# 8-pin_SOIC_TSSOP.net
KiCad netlist of a schematic drawn in EAGLE
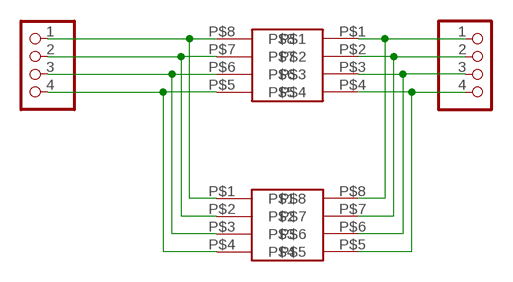
[diagram p0: schematic, sheet 1]

(export (version "E")
  (design (tool "Eeschema 10.0.6"))
  (components
    (comp (ref "CN1")
      (value "PADS-4")
      (footprint "eagle-import:PADS-4")
      (libsource (lib "eagle-import") (part "PADS-4"))
    )
    (comp (ref "CN2")
      (value "PADS-4")
      (footprint "eagle-import:PADS-4")
      (libsource (lib "eagle-import") (part "PADS-4"))
    )
    (comp (ref "U$1")
      (value "8-PINSOIC-NW")
      (footprint "eagle-import:SO8NW")
      (libsource (lib "eagle-import") (part "8-PINSOIC-NW"))
    )
    (comp (ref "U$2")
      (value "8-PINTSSOP")
      (footprint "eagle-import:TSSOP8")
      (libsource (lib "eagle-import") (part "8-PINTSSOP"))
    )
  )
  (nets
    (net (code "1") (name "Net-(CN1-Pad1)") (class "Default")
      (node (ref "CN1") (pin "1") (pinfunction "1_1") (pintype "passive"))
      (node (ref "U$1") (pin "P$8") (pinfunction "P$8_P$8") (pintype "bidirectional"))
      (node (ref "U$2") (pin "P$1") (pinfunction "P$1_P$1") (pintype "bidirectional"))
    )
    (net (code "2") (name "Net-(CN1-Pad2)") (class "Default")
      (node (ref "CN1") (pin "2") (pinfunction "2_2") (pintype "passive"))
      (node (ref "U$1") (pin "P$7") (pinfunction "P$7_P$7") (pintype "bidirectional"))
      (node (ref "U$2") (pin "P$2") (pinfunction "P$2_P$2") (pintype "bidirectional"))
    )
    (net (code "3") (name "Net-(CN1-Pad3)") (class "Default")
      (node (ref "CN1") (pin "3") (pinfunction "3_3") (pintype "passive"))
      (node (ref "U$1") (pin "P$6") (pinfunction "P$6_P$6") (pintype "bidirectional"))
      (node (ref "U$2") (pin "P$3") (pinfunction "P$3_P$3") (pintype "bidirectional"))
    )
    (net (code "4") (name "Net-(CN1-Pad4)") (class "Default")
      (node (ref "CN1") (pin "4") (pinfunction "4_4") (pintype "passive"))
      (node (ref "U$1") (pin "P$5") (pinfunction "P$5_P$5") (pintype "bidirectional"))
      (node (ref "U$2") (pin "P$4") (pinfunction "P$4_P$4") (pintype "bidirectional"))
    )
    (net (code "5") (name "Net-(CN2-Pad1)") (class "Default")
      (node (ref "CN2") (pin "1") (pinfunction "1_1") (pintype "passive"))
      (node (ref "U$1") (pin "P$1") (pinfunction "P$1_P$1") (pintype "bidirectional"))
      (node (ref "U$2") (pin "P$8") (pinfunction "P$8_P$8") (pintype "bidirectional"))
    )
    (net (code "6") (name "Net-(CN2-Pad2)") (class "Default")
      (node (ref "CN2") (pin "2") (pinfunction "2_2") (pintype "passive"))
      (node (ref "U$1") (pin "P$2") (pinfunction "P$2_P$2") (pintype "bidirectional"))
      (node (ref "U$2") (pin "P$7") (pinfunction "P$7_P$7") (pintype "bidirectional"))
    )
    (net (code "7") (name "Net-(CN2-Pad3)") (class "Default")
      (node (ref "CN2") (pin "3") (pinfunction "3_3") (pintype "passive"))
      (node (ref "U$1") (pin "P$3") (pinfunction "P$3_P$3") (pintype "bidirectional"))
      (node (ref "U$2") (pin "P$6") (pinfunction "P$6_P$6") (pintype "bidirectional"))
    )
    (net (code "8") (name "Net-(CN2-Pad4)") (class "Default")
      (node (ref "CN2") (pin "4") (pinfunction "4_4") (pintype "passive"))
      (node (ref "U$1") (pin "P$4") (pinfunction "P$4_P$4") (pintype "bidirectional"))
      (node (ref "U$2") (pin "P$5") (pinfunction "P$5_P$5") (pintype "bidirectional"))
    )
  )
)
